# design.net
KiCad netlist of a schematic drawn in Altium Designer
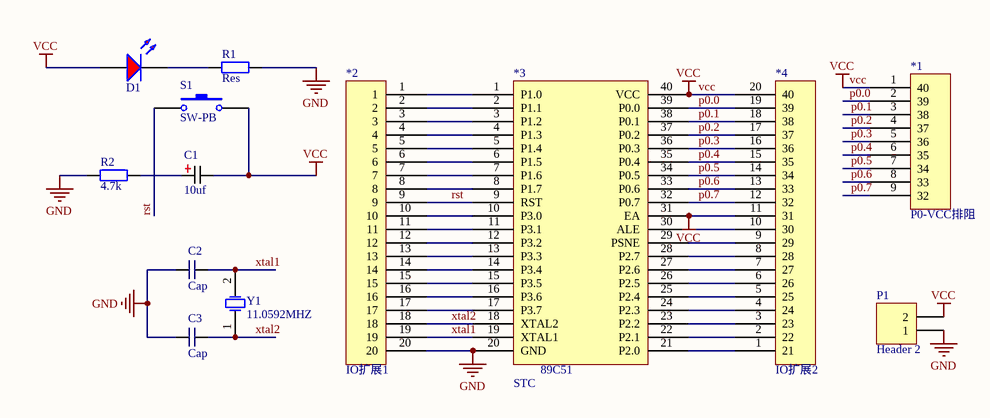
[diagram p0: 最小系统.SchDoc]

(export (version "E")
  (design (tool "Eeschema 10.0.6"))
  (components
    (comp (ref "*1") (value "P0-VCC排阻") (footprint "HDR1X8") (libsource (lib "最小系统") (part "P0-VCC排阻")))
    (comp (ref "*2") (value "IO扩展1") (footprint "HDR1X20") (libsource (lib "最小系统") (part "IO扩展1")))
    (comp (ref "*3") (value "STC") (footprint "DIP403") (libsource (lib "最小系统") (part "STC")))
    (comp (ref "*4") (value "IO扩展2") (footprint "HDR1X20") (libsource (lib "最小系统") (part "IO扩展2")))
    (comp (ref "C1")
      (value "10uf")
      (footprint "CAPR2.54-5.1x3.2")
      (libsource (lib "Schlib1") (part "Cap Pol"))
    )
    (comp (ref "C2") (value "Cap") (footprint "CAPR2.54-5.1x3.2") (libsource (lib "Schlib1") (part "Cap")))
    (comp (ref "C3") (value "Cap") (footprint "CAPR2.54-5.1x3.2") (libsource (lib "Schlib1") (part "Cap")))
    (comp (ref "D1")
      (value "LED0")
      (footprint "RAD-0.1")
      (fields (field (name "PUBLISHER") "Altium Limited"))
      (libsource (lib "Schlib1") (part "LED0"))
    )
    (comp (ref "P1")
      (value "Header 2")
      (footprint "HDR1X2")
      (description "Header, 2-Pin")
      (fields (field (name "PUBLISHER") "Altium Limited"))
      (libsource (lib "Miscellaneous Connectors") (part "Header 2"))
    )
    (comp (ref "R1")
      (value "Res")
      (footprint "AXIAL-0.4")
      (description "Resistor")
      (fields (field (name "PUBLISHER") "Altium Limited"))
      (libsource (lib "Schlib1") (part "Res"))
    )
    (comp (ref "R2")
      (value "4.7k")
      (footprint "AXIAL-0.4")
      (fields (field (name "PUBLISHER") "Altium Limited"))
      (libsource (lib "Miscellaneous Devices") (part "Res2"))
    )
    (comp (ref "S1")
      (value "SW-PB")
      (footprint "MHDR2X2")
      (description "Switch")
      (fields (field (name "PUBLISHER") "Altium Limited"))
      (libsource (lib "Miscellaneous Devices") (part "SW-PB"))
    )
    (comp (ref "Y1")
      (value "11.0592MHZ")
      (footprint "CAPR2.54-5.1x3.2")
      (description "Crystal Oscillator")
      (fields (field (name "PUBLISHER") "Altium Limited"))
      (libsource (lib "Miscellaneous Devices") (part "XTAL"))
    )
  )
  (nets
    (net (code "1") (name "/p0.0") (class "Default")
      (node (ref "*1") (pin "2") (pinfunction "39_2") (pintype "passive"))
      (node (ref "*3") (pin "39") (pinfunction "P0.0_39") (pintype "passive"))
      (node (ref "*4") (pin "19") (pinfunction "39_19") (pintype "passive"))
    )
    (net (code "2") (name "/p0.1") (class "Default")
      (node (ref "*1") (pin "3") (pinfunction "38_3") (pintype "passive"))
      (node (ref "*3") (pin "38") (pinfunction "P0.1_38") (pintype "passive"))
      (node (ref "*4") (pin "18") (pinfunction "38_18") (pintype "passive"))
    )
    (net (code "3") (name "/p0.2") (class "Default")
      (node (ref "*1") (pin "4") (pinfunction "37_4") (pintype "passive"))
      (node (ref "*3") (pin "37") (pinfunction "P0.2_37") (pintype "passive"))
      (node (ref "*4") (pin "17") (pinfunction "37_17") (pintype "passive"))
    )
    (net (code "4") (name "/p0.3") (class "Default")
      (node (ref "*1") (pin "5") (pinfunction "36_5") (pintype "passive"))
      (node (ref "*3") (pin "36") (pinfunction "P0.3_36") (pintype "passive"))
      (node (ref "*4") (pin "16") (pinfunction "36_16") (pintype "passive"))
    )
    (net (code "5") (name "/p0.4") (class "Default")
      (node (ref "*1") (pin "6") (pinfunction "35_6") (pintype "passive"))
      (node (ref "*3") (pin "35") (pinfunction "P0.4_35") (pintype "passive"))
      (node (ref "*4") (pin "15") (pinfunction "35_15") (pintype "passive"))
    )
    (net (code "6") (name "/p0.5") (class "Default")
      (node (ref "*1") (pin "7") (pinfunction "34_7") (pintype "passive"))
      (node (ref "*3") (pin "34") (pinfunction "P0.5_34") (pintype "passive"))
      (node (ref "*4") (pin "14") (pinfunction "34_14") (pintype "passive"))
    )
    (net (code "7") (name "/p0.6") (class "Default")
      (node (ref "*1") (pin "8") (pinfunction "33_8") (pintype "passive"))
      (node (ref "*3") (pin "33") (pinfunction "P0.6_33") (pintype "passive"))
      (node (ref "*4") (pin "13") (pinfunction "33_13") (pintype "passive"))
    )
    (net (code "8") (name "/p0.7") (class "Default")
      (node (ref "*1") (pin "9") (pinfunction "32_9") (pintype "passive"))
      (node (ref "*3") (pin "32") (pinfunction "P0.7_32") (pintype "passive"))
      (node (ref "*4") (pin "12") (pinfunction "32_12") (pintype "passive"))
    )
    (net (code "9") (name "/rst") (class "Default")
      (node (ref "*2") (pin "9") (pinfunction "9_9") (pintype "passive"))
      (node (ref "*3") (pin "9") (pinfunction "RST_9") (pintype "passive"))
      (node (ref "S1") (pin "1") (pinfunction "1_1") (pintype "passive"))
    )
    (net (code "10") (name "/xtal1") (class "Default")
      (node (ref "*2") (pin "19") (pinfunction "19_19") (pintype "passive"))
      (node (ref "*3") (pin "19") (pinfunction "XTAL1_19") (pintype "passive"))
      (node (ref "C2") (pin "2") (pinfunction "2_2") (pintype "passive"))
      (node (ref "Y1") (pin "2") (pinfunction "OSC2_2") (pintype "passive"))
    )
    (net (code "11") (name "/xtal2") (class "Default")
      (node (ref "*2") (pin "18") (pinfunction "18_18") (pintype "passive"))
      (node (ref "*3") (pin "18") (pinfunction "XTAL2_18") (pintype "passive"))
      (node (ref "C3") (pin "2") (pinfunction "2_2") (pintype "passive"))
      (node (ref "Y1") (pin "1") (pinfunction "OSC1_1") (pintype "passive"))
    )
    (net (code "12") (name "GND") (class "Default")
      (node (ref "*2") (pin "20") (pinfunction "20_20") (pintype "passive"))
      (node (ref "*3") (pin "20") (pinfunction "GND_20") (pintype "passive"))
      (node (ref "C2") (pin "1") (pinfunction "1_1") (pintype "passive"))
      (node (ref "C3") (pin "1") (pinfunction "1_1") (pintype "passive"))
      (node (ref "P1") (pin "1") (pinfunction "1_1") (pintype "passive"))
      (node (ref "R1") (pin "2") (pinfunction "2_2") (pintype "passive"))
      (node (ref "R2") (pin "1") (pinfunction "1_1") (pintype "passive"))
    )
    (net (code "13") (name "Net-(*3-ALE)") (class "Default")
      (node (ref "*3") (pin "30") (pinfunction "ALE_30") (pintype "passive"))
      (node (ref "*4") (pin "10") (pinfunction "30_10") (pintype "passive"))
    )
    (net (code "14") (name "Net-(*3-P1.0)") (class "Default")
      (node (ref "*2") (pin "1") (pinfunction "1_1") (pintype "passive"))
      (node (ref "*3") (pin "1") (pinfunction "P1.0_1") (pintype "passive"))
    )
    (net (code "15") (name "Net-(*3-P1.1)") (class "Default")
      (node (ref "*2") (pin "2") (pinfunction "2_2") (pintype "passive"))
      (node (ref "*3") (pin "2") (pinfunction "P1.1_2") (pintype "passive"))
    )
    (net (code "16") (name "Net-(*3-P1.2)") (class "Default")
      (node (ref "*2") (pin "3") (pinfunction "3_3") (pintype "passive"))
      (node (ref "*3") (pin "3") (pinfunction "P1.2_3") (pintype "passive"))
    )
    (net (code "17") (name "Net-(*3-P1.3)") (class "Default")
      (node (ref "*2") (pin "4") (pinfunction "4_4") (pintype "passive"))
      (node (ref "*3") (pin "4") (pinfunction "P1.3_4") (pintype "passive"))
    )
    (net (code "18") (name "Net-(*3-P1.4)") (class "Default")
      (node (ref "*2") (pin "5") (pinfunction "5_5") (pintype "passive"))
      (node (ref "*3") (pin "5") (pinfunction "P1.4_5") (pintype "passive"))
    )
    (net (code "19") (name "Net-(*3-P1.5)") (class "Default")
      (node (ref "*2") (pin "6") (pinfunction "6_6") (pintype "passive"))
      (node (ref "*3") (pin "6") (pinfunction "P1.5_6") (pintype "passive"))
    )
    (net (code "20") (name "Net-(*3-P1.6)") (class "Default")
      (node (ref "*2") (pin "7") (pinfunction "7_7") (pintype "passive"))
      (node (ref "*3") (pin "7") (pinfunction "P1.6_7") (pintype "passive"))
    )
    (net (code "21") (name "Net-(*3-P1.7)") (class "Default")
      (node (ref "*2") (pin "8") (pinfunction "8_8") (pintype "passive"))
      (node (ref "*3") (pin "8") (pinfunction "P1.7_8") (pintype "passive"))
    )
    (net (code "22") (name "Net-(*3-P2.0)") (class "Default")
      (node (ref "*3") (pin "21") (pinfunction "P2.0_21") (pintype "passive"))
      (node (ref "*4") (pin "1") (pinfunction "21_1") (pintype "passive"))
    )
    (net (code "23") (name "Net-(*3-P2.1)") (class "Default")
      (node (ref "*3") (pin "22") (pinfunction "P2.1_22") (pintype "passive"))
      (node (ref "*4") (pin "2") (pinfunction "22_2") (pintype "passive"))
    )
    (net (code "24") (name "Net-(*3-P2.2)") (class "Default")
      (node (ref "*3") (pin "23") (pinfunction "P2.2_23") (pintype "passive"))
      (node (ref "*4") (pin "3") (pinfunction "23_3") (pintype "passive"))
    )
    (net (code "25") (name "Net-(*3-P2.3)") (class "Default")
      (node (ref "*3") (pin "24") (pinfunction "P2.3_24") (pintype "passive"))
      (node (ref "*4") (pin "4") (pinfunction "24_4") (pintype "passive"))
    )
    (net (code "26") (name "Net-(*3-P2.4)") (class "Default")
      (node (ref "*3") (pin "25") (pinfunction "P2.4_25") (pintype "passive"))
      (node (ref "*4") (pin "5") (pinfunction "25_5") (pintype "passive"))
    )
    (net (code "27") (name "Net-(*3-P2.5)") (class "Default")
      (node (ref "*3") (pin "26") (pinfunction "P2.5_26") (pintype "passive"))
      (node (ref "*4") (pin "6") (pinfunction "26_6") (pintype "passive"))
    )
    (net (code "28") (name "Net-(*3-P2.6)") (class "Default")
      (node (ref "*3") (pin "27") (pinfunction "P2.6_27") (pintype "passive"))
      (node (ref "*4") (pin "7") (pinfunction "27_7") (pintype "passive"))
    )
    (net (code "29") (name "Net-(*3-P2.7)") (class "Default")
      (node (ref "*3") (pin "28") (pinfunction "P2.7_28") (pintype "passive"))
      (node (ref "*4") (pin "8") (pinfunction "28_8") (pintype "passive"))
    )
    (net (code "30") (name "Net-(*3-P3.0)") (class "Default")
      (node (ref "*2") (pin "10") (pinfunction "10_10") (pintype "passive"))
      (node (ref "*3") (pin "10") (pinfunction "P3.0_10") (pintype "passive"))
    )
    (net (code "31") (name "Net-(*3-P3.1)") (class "Default")
      (node (ref "*2") (pin "11") (pinfunction "11_11") (pintype "passive"))
      (node (ref "*3") (pin "11") (pinfunction "P3.1_11") (pintype "passive"))
    )
    (net (code "32") (name "Net-(*3-P3.2)") (class "Default")
      (node (ref "*2") (pin "12") (pinfunction "12_12") (pintype "passive"))
      (node (ref "*3") (pin "12") (pinfunction "P3.2_12") (pintype "passive"))
    )
    (net (code "33") (name "Net-(*3-P3.3)") (class "Default")
      (node (ref "*2") (pin "13") (pinfunction "13_13") (pintype "passive"))
      (node (ref "*3") (pin "13") (pinfunction "P3.3_13") (pintype "passive"))
    )
    (net (code "34") (name "Net-(*3-P3.4)") (class "Default")
      (node (ref "*2") (pin "14") (pinfunction "14_14") (pintype "passive"))
      (node (ref "*3") (pin "14") (pinfunction "P3.4_14") (pintype "passive"))
    )
    (net (code "35") (name "Net-(*3-P3.5)") (class "Default")
      (node (ref "*2") (pin "15") (pinfunction "15_15") (pintype "passive"))
      (node (ref "*3") (pin "15") (pinfunction "P3.5_15") (pintype "passive"))
    )
    (net (code "36") (name "Net-(*3-P3.6)") (class "Default")
      (node (ref "*2") (pin "16") (pinfunction "16_16") (pintype "passive"))
      (node (ref "*3") (pin "16") (pinfunction "P3.6_16") (pintype "passive"))
    )
    (net (code "37") (name "Net-(*3-P3.7)") (class "Default")
      (node (ref "*2") (pin "17") (pinfunction "17_17") (pintype "passive"))
      (node (ref "*3") (pin "17") (pinfunction "P3.7_17") (pintype "passive"))
    )
    (net (code "38") (name "Net-(*3-PSNE)") (class "Default")
      (node (ref "*3") (pin "29") (pinfunction "PSNE_29") (pintype "passive"))
      (node (ref "*4") (pin "9") (pinfunction "29_9") (pintype "passive"))
    )
    (net (code "39") (name "Net-(C1-Pad1)") (class "Default")
      (node (ref "C1") (pin "1") (pinfunction "1_1") (pintype "passive"))
      (node (ref "R2") (pin "2") (pinfunction "2_2") (pintype "passive"))
    )
    (net (code "40") (name "Net-(D1-K)") (class "Default")
      (node (ref "D1") (pin "2") (pinfunction "K_2") (pintype "passive"))
      (node (ref "R1") (pin "1") (pinfunction "1_1") (pintype "passive"))
    )
    (net (code "41") (name "VCC") (class "Default")
      (node (ref "*1") (pin "1") (pinfunction "40_1") (pintype "passive"))
      (node (ref "*3") (pin "31") (pinfunction "EA_31") (pintype "passive"))
      (node (ref "*3") (pin "40") (pinfunction "VCC_40") (pintype "passive"))
      (node (ref "*4") (pin "11") (pinfunction "31_11") (pintype "passive"))
      (node (ref "*4") (pin "20") (pinfunction "40_20") (pintype "passive"))
      (node (ref "C1") (pin "2") (pinfunction "2_2") (pintype "passive"))
      (node (ref "D1") (pin "1") (pinfunction "A_1") (pintype "passive"))
      (node (ref "P1") (pin "2") (pinfunction "2_2") (pintype "passive"))
      (node (ref "S1") (pin "2") (pinfunction "2_2") (pintype "passive"))
    )
  )
)
